# pic_socket.net
KiCad netlist of a schematic drawn in EAGLE
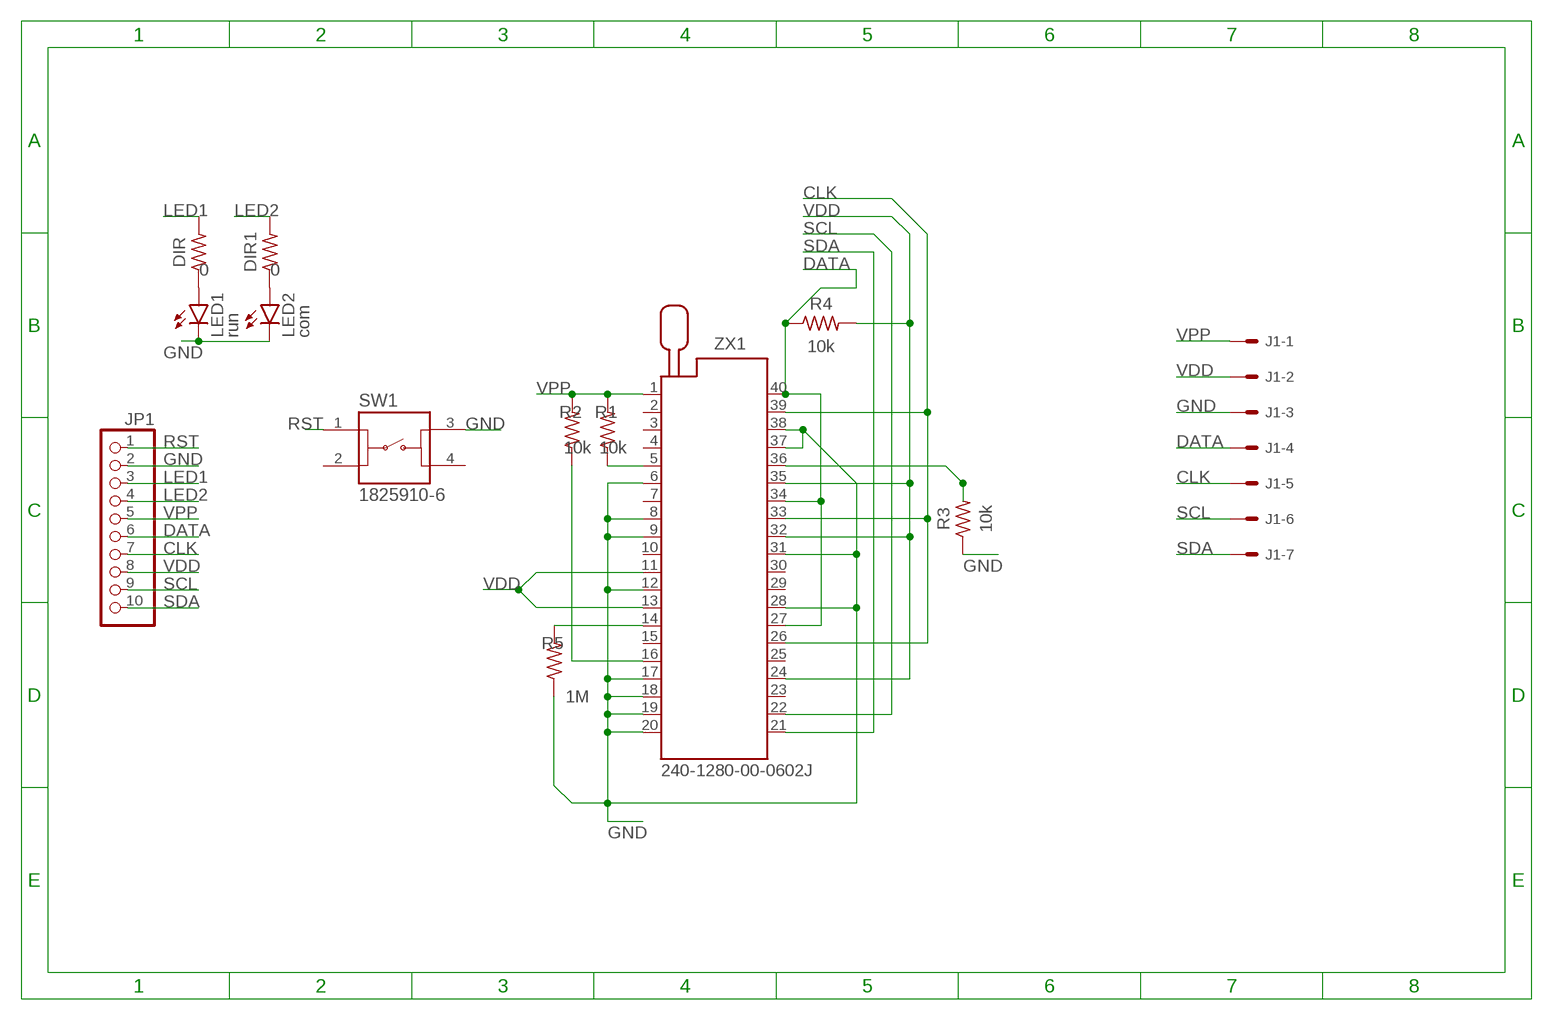
[diagram p0: schematic, sheet 1]

(export (version "E")
  (design (tool "Eeschema 10.0.6"))
  (components
    (comp (ref "DIR")
      (value "0")
      (footprint "eagle-import:RESC3216X70")
      (libsource (lib "eagle-import") (part "R-USCHIP-1206(3216-METRIC)_"))
    )
    (comp (ref "DIR1")
      (value "0")
      (footprint "eagle-import:RESC3216X70")
      (libsource (lib "eagle-import") (part "R-USCHIP-1206(3216-METRIC)_"))
    )
    (comp (ref "J1")
      (value "22-05-7078-07")
      (footprint "eagle-import:7395-07")
      (fields (field (name "MF") "MOLEX"))
      (libsource (lib "eagle-import") (part "22-?-0705-7078"))
    )
    (comp (ref "JP1")
      (value "PINHD-1X10")
      (footprint "eagle-import:1X10")
      (libsource (lib "eagle-import") (part "PINHD-1X10"))
    )
    (comp (ref "LED1")
      (value "run")
      (footprint "eagle-import:1206")
      (libsource (lib "eagle-import") (part "LEDSMT1206"))
    )
    (comp (ref "LED2")
      (value "com")
      (footprint "eagle-import:1206")
      (libsource (lib "eagle-import") (part "LEDSMT1206"))
    )
    (comp (ref "R1")
      (value "10k")
      (footprint "eagle-import:RESC3216X70")
      (libsource (lib "eagle-import") (part "R-USCHIP-1206(3216-METRIC)_"))
    )
    (comp (ref "R2")
      (value "10k")
      (footprint "eagle-import:RESC3216X70")
      (libsource (lib "eagle-import") (part "R-USCHIP-1206(3216-METRIC)_"))
    )
    (comp (ref "R3")
      (value "10k")
      (footprint "eagle-import:RESC3216X70")
      (libsource (lib "eagle-import") (part "R-USCHIP-1206(3216-METRIC)_"))
    )
    (comp (ref "R4")
      (value "10k")
      (footprint "eagle-import:RESC3216X70")
      (libsource (lib "eagle-import") (part "R-USCHIP-1206(3216-METRIC)_"))
    )
    (comp (ref "R5")
      (value "1M")
      (footprint "eagle-import:RESC3216X70")
      (libsource (lib "eagle-import") (part "R-USCHIP-1206(3216-METRIC)_"))
    )
    (comp (ref "SW1")
      (value "1825910-6")
      (footprint "eagle-import:1825910-6")
      (fields
        (field (name "DIGIKEY_PART_NUMBER") "450-1650-ND")
        (field (name "MANUFACTURER") "TE Connectivity ALCOSWITCH Switches")
        (field (name "CREATED_BY") " PCBLayout.com")
      )
      (libsource (lib "eagle-import") (part "1825910-6"))
    )
    (comp (ref "ZX1")
      (value "240-1280-00-0602J")
      (footprint "eagle-import:240-1280-00-0602J")
      (fields (field (name "MF") "3M"))
      (libsource (lib "eagle-import") (part "240-?-00-0602J1280"))
    )
  )
  (nets
    (net (code "1") (name "/CLK") (class "Default")
      (node (ref "J1") (pin "5") (pinfunction "S_5") (pintype "passive"))
      (node (ref "JP1") (pin "7") (pinfunction "7_7") (pintype "passive"))
      (node (ref "ZX1") (pin "26") (pinfunction "26_26") (pintype "passive"))
      (node (ref "ZX1") (pin "33") (pinfunction "33_33") (pintype "passive"))
      (node (ref "ZX1") (pin "39") (pinfunction "39_39") (pintype "passive"))
    )
    (net (code "2") (name "/DATA") (class "Default")
      (node (ref "J1") (pin "4") (pinfunction "S_4") (pintype "passive"))
      (node (ref "JP1") (pin "6") (pinfunction "6_6") (pintype "passive"))
      (node (ref "R4") (pin "1") (pinfunction "1_1") (pintype "passive"))
      (node (ref "ZX1") (pin "27") (pinfunction "27_27") (pintype "passive"))
      (node (ref "ZX1") (pin "34") (pinfunction "34_34") (pintype "passive"))
      (node (ref "ZX1") (pin "40") (pinfunction "40_40") (pintype "passive"))
    )
    (net (code "3") (name "/GND") (class "Default")
      (node (ref "J1") (pin "3") (pinfunction "S_3") (pintype "passive"))
      (node (ref "JP1") (pin "2") (pinfunction "2_2") (pintype "passive"))
      (node (ref "LED1") (pin "C") (pinfunction "C_C") (pintype "passive"))
      (node (ref "LED2") (pin "C") (pinfunction "C_C") (pintype "passive"))
      (node (ref "R3") (pin "1") (pinfunction "1_1") (pintype "passive"))
      (node (ref "R5") (pin "1") (pinfunction "1_1") (pintype "passive"))
      (node (ref "SW1") (pin "3") (pinfunction "3_3") (pintype "passive"))
      (node (ref "ZX1") (pin "12") (pinfunction "12_12") (pintype "passive"))
      (node (ref "ZX1") (pin "17") (pinfunction "17_17") (pintype "passive"))
      (node (ref "ZX1") (pin "18") (pinfunction "18_18") (pintype "passive"))
      (node (ref "ZX1") (pin "19") (pinfunction "19_19") (pintype "passive"))
      (node (ref "ZX1") (pin "20") (pinfunction "20_20") (pintype "passive"))
      (node (ref "ZX1") (pin "28") (pinfunction "28_28") (pintype "passive"))
      (node (ref "ZX1") (pin "31") (pinfunction "31_31") (pintype "passive"))
      (node (ref "ZX1") (pin "37") (pinfunction "37_37") (pintype "passive"))
      (node (ref "ZX1") (pin "38") (pinfunction "38_38") (pintype "passive"))
      (node (ref "ZX1") (pin "6") (pinfunction "6_6") (pintype "passive"))
      (node (ref "ZX1") (pin "8") (pinfunction "8_8") (pintype "passive"))
      (node (ref "ZX1") (pin "9") (pinfunction "9_9") (pintype "passive"))
    )
    (net (code "4") (name "/LED1") (class "Default")
      (node (ref "DIR") (pin "2") (pinfunction "2_2") (pintype "passive"))
      (node (ref "JP1") (pin "3") (pinfunction "3_3") (pintype "passive"))
    )
    (net (code "5") (name "/LED2") (class "Default")
      (node (ref "DIR1") (pin "2") (pinfunction "2_2") (pintype "passive"))
      (node (ref "JP1") (pin "4") (pinfunction "4_4") (pintype "passive"))
    )
    (net (code "6") (name "/RST") (class "Default")
      (node (ref "JP1") (pin "1") (pinfunction "1_1") (pintype "passive"))
      (node (ref "SW1") (pin "1") (pinfunction "1_1") (pintype "passive"))
    )
    (net (code "7") (name "/SCL") (class "Default")
      (node (ref "J1") (pin "6") (pinfunction "S_6") (pintype "passive"))
      (node (ref "JP1") (pin "9") (pinfunction "9_9") (pintype "passive"))
      (node (ref "ZX1") (pin "22") (pinfunction "22_22") (pintype "passive"))
    )
    (net (code "8") (name "/SDA") (class "Default")
      (node (ref "J1") (pin "7") (pinfunction "S_7") (pintype "passive"))
      (node (ref "JP1") (pin "10") (pinfunction "10_10") (pintype "passive"))
      (node (ref "ZX1") (pin "21") (pinfunction "21_21") (pintype "passive"))
    )
    (net (code "9") (name "/VDD") (class "Default")
      (node (ref "J1") (pin "2") (pinfunction "S_2") (pintype "passive"))
      (node (ref "JP1") (pin "8") (pinfunction "8_8") (pintype "passive"))
      (node (ref "R4") (pin "2") (pinfunction "2_2") (pintype "passive"))
      (node (ref "ZX1") (pin "11") (pinfunction "11_11") (pintype "passive"))
      (node (ref "ZX1") (pin "13") (pinfunction "13_13") (pintype "passive"))
      (node (ref "ZX1") (pin "24") (pinfunction "24_24") (pintype "passive"))
      (node (ref "ZX1") (pin "32") (pinfunction "32_32") (pintype "passive"))
      (node (ref "ZX1") (pin "35") (pinfunction "35_35") (pintype "passive"))
    )
    (net (code "10") (name "/VPP") (class "Default")
      (node (ref "J1") (pin "1") (pinfunction "S_1") (pintype "passive"))
      (node (ref "JP1") (pin "5") (pinfunction "5_5") (pintype "passive"))
      (node (ref "R1") (pin "2") (pinfunction "2_2") (pintype "passive"))
      (node (ref "R2") (pin "2") (pinfunction "2_2") (pintype "passive"))
      (node (ref "ZX1") (pin "1") (pinfunction "1_1") (pintype "passive"))
    )
    (net (code "11") (name "Net-(DIR-Pad1)") (class "Default")
      (node (ref "DIR") (pin "1") (pinfunction "1_1") (pintype "passive"))
      (node (ref "LED1") (pin "A") (pinfunction "A_A") (pintype "passive"))
    )
    (net (code "12") (name "Net-(DIR1-Pad1)") (class "Default")
      (node (ref "DIR1") (pin "1") (pinfunction "1_1") (pintype "passive"))
      (node (ref "LED2") (pin "A") (pinfunction "A_A") (pintype "passive"))
    )
    (net (code "13") (name "Net-(R1-Pad1)") (class "Default")
      (node (ref "R1") (pin "1") (pinfunction "1_1") (pintype "passive"))
      (node (ref "ZX1") (pin "5") (pinfunction "5_5") (pintype "passive"))
    )
    (net (code "14") (name "Net-(R2-Pad1)") (class "Default")
      (node (ref "R2") (pin "1") (pinfunction "1_1") (pintype "passive"))
      (node (ref "ZX1") (pin "16") (pinfunction "16_16") (pintype "passive"))
    )
    (net (code "15") (name "Net-(R3-Pad2)") (class "Default")
      (node (ref "R3") (pin "2") (pinfunction "2_2") (pintype "passive"))
      (node (ref "ZX1") (pin "36") (pinfunction "36_36") (pintype "passive"))
    )
    (net (code "16") (name "Net-(R5-Pad2)") (class "Default")
      (node (ref "R5") (pin "2") (pinfunction "2_2") (pintype "passive"))
      (node (ref "ZX1") (pin "14") (pinfunction "14_14") (pintype "passive"))
    )
    (net (code "17") (name "unconnected-(SW1-Pad2)") (class "Default")
      (node (ref "SW1") (pin "2") (pinfunction "2_2") (pintype "passive"))
    )
    (net (code "18") (name "unconnected-(SW1-Pad4)") (class "Default")
      (node (ref "SW1") (pin "4") (pinfunction "4_4") (pintype "passive"))
    )
    (net (code "19") (name "unconnected-(ZX1-Pad2)") (class "Default")
      (node (ref "ZX1") (pin "2") (pinfunction "2_2") (pintype "passive"))
    )
    (net (code "20") (name "unconnected-(ZX1-Pad3)") (class "Default")
      (node (ref "ZX1") (pin "3") (pinfunction "3_3") (pintype "passive"))
    )
    (net (code "21") (name "unconnected-(ZX1-Pad4)") (class "Default")
      (node (ref "ZX1") (pin "4") (pinfunction "4_4") (pintype "passive"))
    )
    (net (code "22") (name "unconnected-(ZX1-Pad7)") (class "Default")
      (node (ref "ZX1") (pin "7") (pinfunction "7_7") (pintype "passive"))
    )
    (net (code "23") (name "unconnected-(ZX1-Pad10)") (class "Default")
      (node (ref "ZX1") (pin "10") (pinfunction "10_10") (pintype "passive"))
    )
    (net (code "24") (name "unconnected-(ZX1-Pad15)") (class "Default")
      (node (ref "ZX1") (pin "15") (pinfunction "15_15") (pintype "passive"))
    )
    (net (code "25") (name "unconnected-(ZX1-Pad23)") (class "Default")
      (node (ref "ZX1") (pin "23") (pinfunction "23_23") (pintype "passive"))
    )
    (net (code "26") (name "unconnected-(ZX1-Pad25)") (class "Default")
      (node (ref "ZX1") (pin "25") (pinfunction "25_25") (pintype "passive"))
    )
    (net (code "27") (name "unconnected-(ZX1-Pad29)") (class "Default")
      (node (ref "ZX1") (pin "29") (pinfunction "29_29") (pintype "passive"))
    )
    (net (code "28") (name "unconnected-(ZX1-Pad30)") (class "Default")
      (node (ref "ZX1") (pin "30") (pinfunction "30_30") (pintype "passive"))
    )
  )
)
